# Schematics.net
KiCad netlist of a schematic drawn in EAGLE
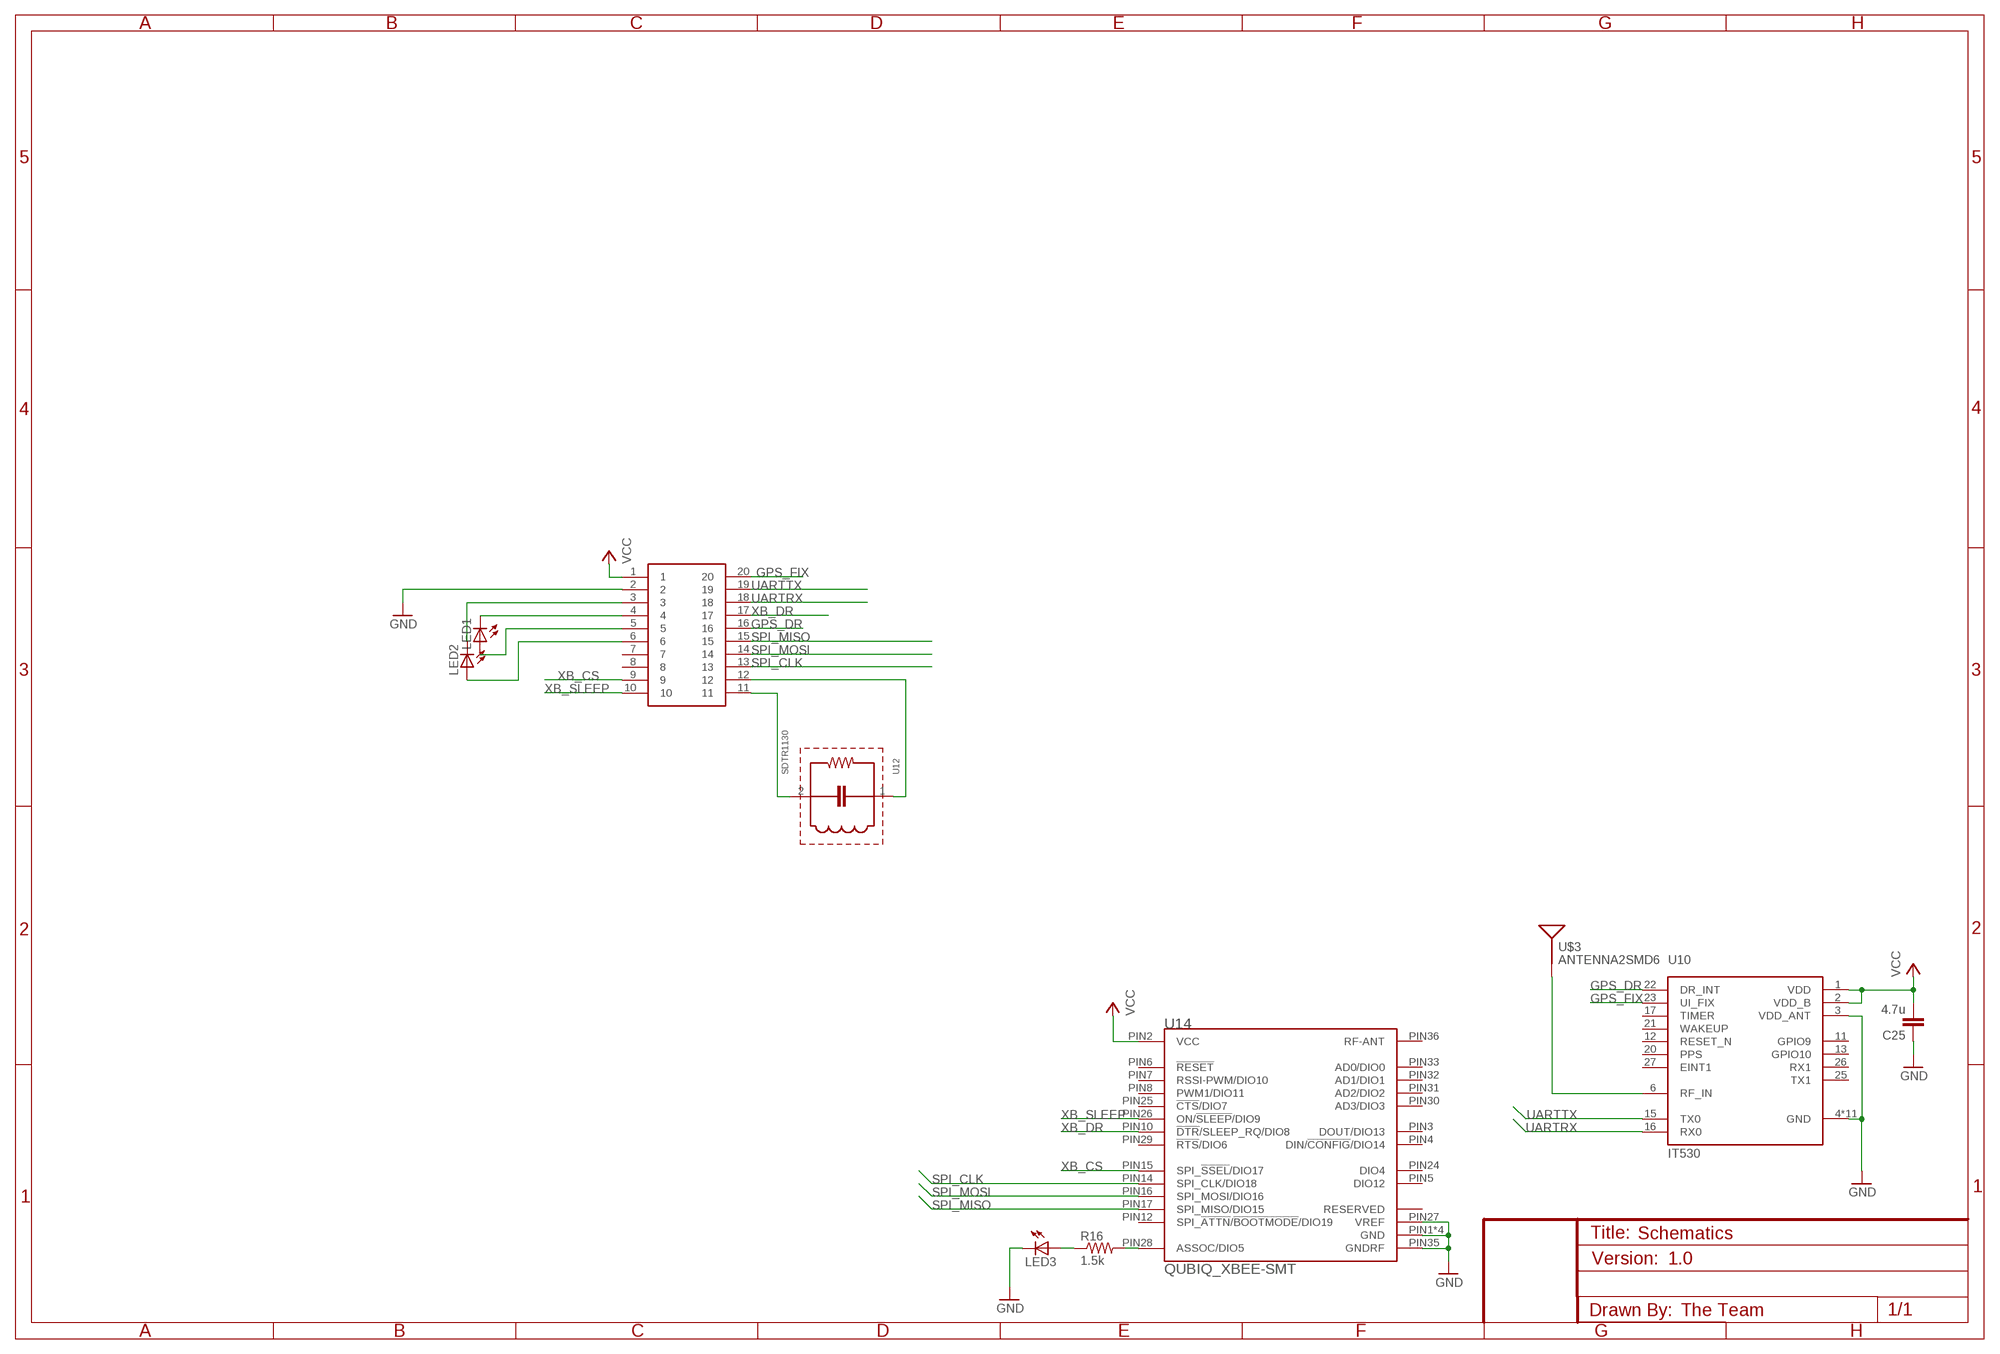
[diagram p0: schematic, sheet 1]

(export (version "E")
  (design (tool "Eeschema 10.0.6"))
  (components
    (comp (ref "C25")
      (value "4.7u")
      (footprint "eagle-import:C0603")
      (libsource (lib "eagle-import") (part "C-EUC0603"))
    )
    (comp (ref "LED1")
      (value "LED")
      (footprint "eagle-import:SMARTLED-TTW")
      (libsource (lib "eagle-import") (part "LED"))
    )
    (comp (ref "LED2")
      (value "LED")
      (footprint "eagle-import:SMARTLED-TTW")
      (libsource (lib "eagle-import") (part "LED"))
    )
    (comp (ref "LED3")
      (value "LED")
      (footprint "eagle-import:SMARTLED-TTW")
      (libsource (lib "eagle-import") (part "LED"))
    )
    (comp (ref "R16")
      (value "1.5k")
      (footprint "eagle-import:R0603")
      (libsource (lib "eagle-import") (part "R-US_R0603"))
    )
    (comp (ref "U$2")
      (value "20-HEAD")
      (footprint "eagle-import:20-HEAD")
      (libsource (lib "eagle-import") (part "20-HEAD"))
    )
    (comp (ref "U$3")
      (value "ANTENNA2SMD6")
      (footprint "eagle-import:ANTENNA-CHIP6")
      (libsource (lib "eagle-import") (part "ANTENNA2SMD6"))
    )
    (comp (ref "U10")
      (value "IT530")
      (footprint "eagle-import:IT530")
      (libsource (lib "eagle-import") (part "IT530"))
    )
    (comp (ref "U12")
      (value "SDTR1130")
      (footprint "eagle-import:SDTR1130-SMD")
      (libsource (lib "eagle-import") (part "SDTR1130"))
    )
    (comp (ref "U14")
      (value "QUBIQ_XBEE-SMT")
      (footprint "eagle-import:QUBIQ_FLAT-RF")
      (libsource (lib "eagle-import") (part "QUBIQ_XBEE-SMT"))
    )
  )
  (nets
    (net (code "1") (name "/GPS_DR") (class "Default")
      (node (ref "U$2") (pin "16") (pinfunction "16_16") (pintype "bidirectional"))
      (node (ref "U10") (pin "22") (pinfunction "DR_INT_22") (pintype "bidirectional"))
    )
    (net (code "2") (name "/GPS_FIX") (class "Default")
      (node (ref "U$2") (pin "20") (pinfunction "20_20") (pintype "bidirectional"))
      (node (ref "U10") (pin "23") (pinfunction "UI_FIX_23") (pintype "bidirectional"))
    )
    (net (code "3") (name "/SPI_CLK") (class "Default")
      (node (ref "U$2") (pin "13") (pinfunction "13_13") (pintype "bidirectional"))
      (node (ref "U14") (pin "PIN14") (pinfunction "SPI_CLK/DIO18_PIN14") (pintype "bidirectional"))
    )
    (net (code "4") (name "/SPI_MISO") (class "Default")
      (node (ref "U$2") (pin "15") (pinfunction "15_15") (pintype "bidirectional"))
      (node (ref "U14") (pin "PIN17") (pinfunction "SPI_MISO/DIO15_PIN17") (pintype "bidirectional"))
    )
    (net (code "5") (name "/SPI_MOSI") (class "Default")
      (node (ref "U$2") (pin "14") (pinfunction "14_14") (pintype "bidirectional"))
      (node (ref "U14") (pin "PIN16") (pinfunction "SPI_MOSI/DIO16_PIN16") (pintype "bidirectional"))
    )
    (net (code "6") (name "/UARTRX") (class "Default")
      (node (ref "U$2") (pin "18") (pinfunction "18_18") (pintype "bidirectional"))
      (node (ref "U10") (pin "16") (pinfunction "RX0_16") (pintype "bidirectional"))
    )
    (net (code "7") (name "/UARTTX") (class "Default")
      (node (ref "U$2") (pin "19") (pinfunction "19_19") (pintype "bidirectional"))
      (node (ref "U10") (pin "15") (pinfunction "TX0_15") (pintype "bidirectional"))
    )
    (net (code "8") (name "/XB_CS") (class "Default")
      (node (ref "U$2") (pin "9") (pinfunction "9_9") (pintype "bidirectional"))
      (node (ref "U14") (pin "PIN15") (pinfunction "SPI_~{SSEL}/DIO17_PIN15") (pintype "bidirectional"))
    )
    (net (code "9") (name "/XB_DR") (class "Default")
      (node (ref "U$2") (pin "17") (pinfunction "17_17") (pintype "bidirectional"))
      (node (ref "U14") (pin "PIN10") (pinfunction "~{DTR}/SLEEP_RQ/DIO8_PIN10") (pintype "bidirectional"))
    )
    (net (code "10") (name "/XB_SLEEP") (class "Default")
      (node (ref "U$2") (pin "10") (pinfunction "10_10") (pintype "bidirectional"))
      (node (ref "U14") (pin "PIN26") (pinfunction "ON/~{SLEEP}/DIO9_PIN26") (pintype "bidirectional"))
    )
    (net (code "11") (name "GND") (class "Default")
      (node (ref "C25") (pin "1") (pinfunction "1_1") (pintype "passive"))
      (node (ref "LED3") (pin "C@1") (pinfunction "C_C@1") (pintype "passive"))
      (node (ref "U$2") (pin "2") (pinfunction "2_2") (pintype "bidirectional"))
      (node (ref "U10") (pin "10") (pinfunction "GND_10") (pintype "bidirectional"))
      (node (ref "U10") (pin "14") (pinfunction "GND_14") (pintype "bidirectional"))
      (node (ref "U10") (pin "18") (pinfunction "GND_18") (pintype "bidirectional"))
      (node (ref "U10") (pin "19") (pinfunction "GND_19") (pintype "bidirectional"))
      (node (ref "U10") (pin "24") (pinfunction "GND_24") (pintype "bidirectional"))
      (node (ref "U10") (pin "28") (pinfunction "GND_28") (pintype "bidirectional"))
      (node (ref "U10") (pin "3") (pinfunction "VDD_ANT_3") (pintype "bidirectional"))
      (node (ref "U10") (pin "4") (pinfunction "GND_4") (pintype "bidirectional"))
      (node (ref "U10") (pin "5") (pinfunction "GND_5") (pintype "bidirectional"))
      (node (ref "U10") (pin "7") (pinfunction "GND_7") (pintype "bidirectional"))
      (node (ref "U10") (pin "8") (pinfunction "GND_8") (pintype "bidirectional"))
      (node (ref "U10") (pin "9") (pinfunction "GND_9") (pintype "bidirectional"))
      (node (ref "U14") (pin "PIN1") (pinfunction "GND_PIN1") (pintype "power_in"))
      (node (ref "U14") (pin "PIN11") (pinfunction "GND_PIN11") (pintype "power_in"))
      (node (ref "U14") (pin "PIN13") (pinfunction "GND_PIN13") (pintype "power_in"))
      (node (ref "U14") (pin "PIN22") (pinfunction "GND_PIN22") (pintype "power_in"))
      (node (ref "U14") (pin "PIN27") (pinfunction "VREF_PIN27") (pintype "bidirectional"))
      (node (ref "U14") (pin "PIN35") (pinfunction "GNDRF_PIN35") (pintype "bidirectional"))
    )
    (net (code "12") (name "Net-(LED1-A)") (class "Default")
      (node (ref "LED1") (pin "A@1") (pinfunction "A_A@1") (pintype "passive"))
      (node (ref "U$2") (pin "5") (pinfunction "5_5") (pintype "bidirectional"))
    )
    (net (code "13") (name "Net-(LED1-C)") (class "Default")
      (node (ref "LED1") (pin "C@1") (pinfunction "C_C@1") (pintype "passive"))
      (node (ref "U$2") (pin "4") (pinfunction "4_4") (pintype "bidirectional"))
    )
    (net (code "14") (name "Net-(LED2-A)") (class "Default")
      (node (ref "LED2") (pin "A@1") (pinfunction "A_A@1") (pintype "passive"))
      (node (ref "U$2") (pin "6") (pinfunction "6_6") (pintype "bidirectional"))
    )
    (net (code "15") (name "Net-(LED2-C)") (class "Default")
      (node (ref "LED2") (pin "C@1") (pinfunction "C_C@1") (pintype "passive"))
      (node (ref "U$2") (pin "3") (pinfunction "3_3") (pintype "bidirectional"))
    )
    (net (code "16") (name "Net-(LED3-A)") (class "Default")
      (node (ref "LED3") (pin "A@1") (pinfunction "A_A@1") (pintype "passive"))
      (node (ref "R16") (pin "1") (pinfunction "1_1") (pintype "passive"))
    )
    (net (code "17") (name "Net-(U$2-Pad11)") (class "Default")
      (node (ref "U$2") (pin "11") (pinfunction "11_11") (pintype "bidirectional"))
      (node (ref "U12") (pin "2") (pinfunction "2_2") (pintype "bidirectional"))
    )
    (net (code "18") (name "Net-(U$2-Pad12)") (class "Default")
      (node (ref "U$2") (pin "12") (pinfunction "12_12") (pintype "bidirectional"))
      (node (ref "U12") (pin "1") (pinfunction "1_1") (pintype "bidirectional"))
    )
    (net (code "19") (name "Net-(U$3-SIGNAL)") (class "Default")
      (node (ref "U$3") (pin "1") (pinfunction "SIGNAL_1") (pintype "bidirectional"))
      (node (ref "U10") (pin "6") (pinfunction "RF_IN_6") (pintype "bidirectional"))
    )
    (net (code "20") (name "Net-(U14-ASSOC{slash}DIO5)") (class "Default")
      (node (ref "R16") (pin "2") (pinfunction "2_2") (pintype "passive"))
      (node (ref "U14") (pin "PIN28") (pinfunction "ASSOC/DIO5_PIN28") (pintype "bidirectional"))
    )
    (net (code "21") (name "VCC") (class "Default")
      (node (ref "C25") (pin "2") (pinfunction "2_2") (pintype "passive"))
      (node (ref "U$2") (pin "1") (pinfunction "1_1") (pintype "bidirectional"))
      (node (ref "U10") (pin "1") (pinfunction "VDD_1") (pintype "bidirectional"))
      (node (ref "U10") (pin "2") (pinfunction "VDD_B_2") (pintype "bidirectional"))
      (node (ref "U14") (pin "PIN2") (pinfunction "VCC_PIN2") (pintype "bidirectional"))
    )
    (net (code "22") (name "unconnected-(U$2-Pad7)") (class "Default")
      (node (ref "U$2") (pin "7") (pinfunction "7_7") (pintype "bidirectional"))
    )
    (net (code "23") (name "unconnected-(U$2-Pad8)") (class "Default")
      (node (ref "U$2") (pin "8") (pinfunction "8_8") (pintype "bidirectional"))
    )
    (net (code "24") (name "unconnected-(U10-EINT1-Pad27)") (class "Default")
      (node (ref "U10") (pin "27") (pinfunction "EINT1_27") (pintype "bidirectional"))
    )
    (net (code "25") (name "unconnected-(U10-GPIO9-Pad11)") (class "Default")
      (node (ref "U10") (pin "11") (pinfunction "GPIO9_11") (pintype "bidirectional"))
    )
    (net (code "26") (name "unconnected-(U10-GPIO10-Pad13)") (class "Default")
      (node (ref "U10") (pin "13") (pinfunction "GPIO10_13") (pintype "bidirectional"))
    )
    (net (code "27") (name "unconnected-(U10-PPS-Pad20)") (class "Default")
      (node (ref "U10") (pin "20") (pinfunction "PPS_20") (pintype "bidirectional"))
    )
    (net (code "28") (name "unconnected-(U10-RESET_N-Pad12)") (class "Default")
      (node (ref "U10") (pin "12") (pinfunction "RESET_N_12") (pintype "bidirectional"))
    )
    (net (code "29") (name "unconnected-(U10-RX1-Pad26)") (class "Default")
      (node (ref "U10") (pin "26") (pinfunction "RX1_26") (pintype "bidirectional"))
    )
    (net (code "30") (name "unconnected-(U10-TIMER-Pad17)") (class "Default")
      (node (ref "U10") (pin "17") (pinfunction "TIMER_17") (pintype "bidirectional"))
    )
    (net (code "31") (name "unconnected-(U10-TX1-Pad25)") (class "Default")
      (node (ref "U10") (pin "25") (pinfunction "TX1_25") (pintype "bidirectional"))
    )
    (net (code "32") (name "unconnected-(U10-WAKEUP-Pad21)") (class "Default")
      (node (ref "U10") (pin "21") (pinfunction "WAKEUP_21") (pintype "bidirectional"))
    )
    (net (code "33") (name "unconnected-(U14-AD0{slash}DIO0-PadPIN33)") (class "Default")
      (node (ref "U14") (pin "PIN33") (pinfunction "AD0/DIO0_PIN33") (pintype "bidirectional"))
    )
    (net (code "34") (name "unconnected-(U14-AD1{slash}DIO1-PadPIN32)") (class "Default")
      (node (ref "U14") (pin "PIN32") (pinfunction "AD1/DIO1_PIN32") (pintype "bidirectional"))
    )
    (net (code "35") (name "unconnected-(U14-AD2{slash}DIO2-PadPIN31)") (class "Default")
      (node (ref "U14") (pin "PIN31") (pinfunction "AD2/DIO2_PIN31") (pintype "bidirectional"))
    )
    (net (code "36") (name "unconnected-(U14-AD3{slash}DIO3-PadPIN30)") (class "Default")
      (node (ref "U14") (pin "PIN30") (pinfunction "AD3/DIO3_PIN30") (pintype "bidirectional"))
    )
    (net (code "37") (name "unconnected-(U14-DIN{slash}~{CONFIG}{slash}DIO14-PadPIN4)") (class "Default")
      (node (ref "U14") (pin "PIN4") (pinfunction "DIN/~{CONFIG}/DIO14_PIN4") (pintype "bidirectional"))
    )
    (net (code "38") (name "unconnected-(U14-DIO4-PadPIN24)") (class "Default")
      (node (ref "U14") (pin "PIN24") (pinfunction "DIO4_PIN24") (pintype "bidirectional"))
    )
    (net (code "39") (name "unconnected-(U14-DIO12-PadPIN5)") (class "Default")
      (node (ref "U14") (pin "PIN5") (pinfunction "DIO12_PIN5") (pintype "bidirectional"))
    )
    (net (code "40") (name "unconnected-(U14-DOUT{slash}DIO13-PadPIN3)") (class "Default")
      (node (ref "U14") (pin "PIN3") (pinfunction "DOUT/DIO13_PIN3") (pintype "bidirectional"))
    )
    (net (code "41") (name "unconnected-(U14-PWM1{slash}DIO11-PadPIN8)") (class "Default")
      (node (ref "U14") (pin "PIN8") (pinfunction "PWM1/DIO11_PIN8") (pintype "bidirectional"))
    )
    (net (code "42") (name "unconnected-(U14-RESERVED-PadPIN9)") (class "Default")
      (node (ref "U14") (pin "PIN9") (pinfunction "RESERVED_PIN9") (pintype "no_connect"))
    )
    (net (code "43") (name "unconnected-(U14-RESERVED-PadPIN18)") (class "Default")
      (node (ref "U14") (pin "PIN18") (pinfunction "RESERVED_PIN18") (pintype "no_connect"))
    )
    (net (code "44") (name "unconnected-(U14-RESERVED-PadPIN19)") (class "Default")
      (node (ref "U14") (pin "PIN19") (pinfunction "RESERVED_PIN19") (pintype "no_connect"))
    )
    (net (code "45") (name "unconnected-(U14-RESERVED-PadPIN20)") (class "Default")
      (node (ref "U14") (pin "PIN20") (pinfunction "RESERVED_PIN20") (pintype "no_connect"))
    )
    (net (code "46") (name "unconnected-(U14-RESERVED-PadPIN21)") (class "Default")
      (node (ref "U14") (pin "PIN21") (pinfunction "RESERVED_PIN21") (pintype "no_connect"))
    )
    (net (code "47") (name "unconnected-(U14-RESERVED-PadPIN23)") (class "Default")
      (node (ref "U14") (pin "PIN23") (pinfunction "RESERVED_PIN23") (pintype "no_connect"))
    )
    (net (code "48") (name "unconnected-(U14-RESERVED-PadPIN34)") (class "Default")
      (node (ref "U14") (pin "PIN34") (pinfunction "RESERVED_PIN34") (pintype "no_connect"))
    )
    (net (code "49") (name "unconnected-(U14-RESERVED-PadPIN37)") (class "Default")
      (node (ref "U14") (pin "PIN37") (pinfunction "RESERVED_PIN37") (pintype "no_connect"))
    )
    (net (code "50") (name "unconnected-(U14-RF-ANT-PadPIN36)") (class "Default")
      (node (ref "U14") (pin "PIN36") (pinfunction "RF-ANT_PIN36") (pintype "bidirectional"))
    )
    (net (code "51") (name "unconnected-(U14-RSSI-PWM{slash}DIO10-PadPIN7)") (class "Default")
      (node (ref "U14") (pin "PIN7") (pinfunction "RSSI-PWM/DIO10_PIN7") (pintype "bidirectional"))
    )
    (net (code "52") (name "unconnected-(U14-SPI_~{ATTN}{slash}~{BOOTMODE}{slash}DIO19-PadPIN12)") (class "Default")
      (node (ref "U14") (pin "PIN12") (pinfunction "SPI_~{ATTN}/~{BOOTMODE}/DIO19_PIN12") (pintype "bidirectional"))
    )
    (net (code "53") (name "unconnected-(U14-~{CTS}{slash}DIO7-PadPIN25)") (class "Default")
      (node (ref "U14") (pin "PIN25") (pinfunction "~{CTS}/DIO7_PIN25") (pintype "bidirectional"))
    )
    (net (code "54") (name "unconnected-(U14-~{RESET}-PadPIN6)") (class "Default")
      (node (ref "U14") (pin "PIN6") (pinfunction "~{RESET}_PIN6") (pintype "bidirectional"))
    )
    (net (code "55") (name "unconnected-(U14-~{RTS}{slash}DIO6-PadPIN29)") (class "Default")
      (node (ref "U14") (pin "PIN29") (pinfunction "~{RTS}/DIO6_PIN29") (pintype "bidirectional"))
    )
  )
)
